# BQ27541.net
KiCad netlist of a schematic drawn in EAGLE
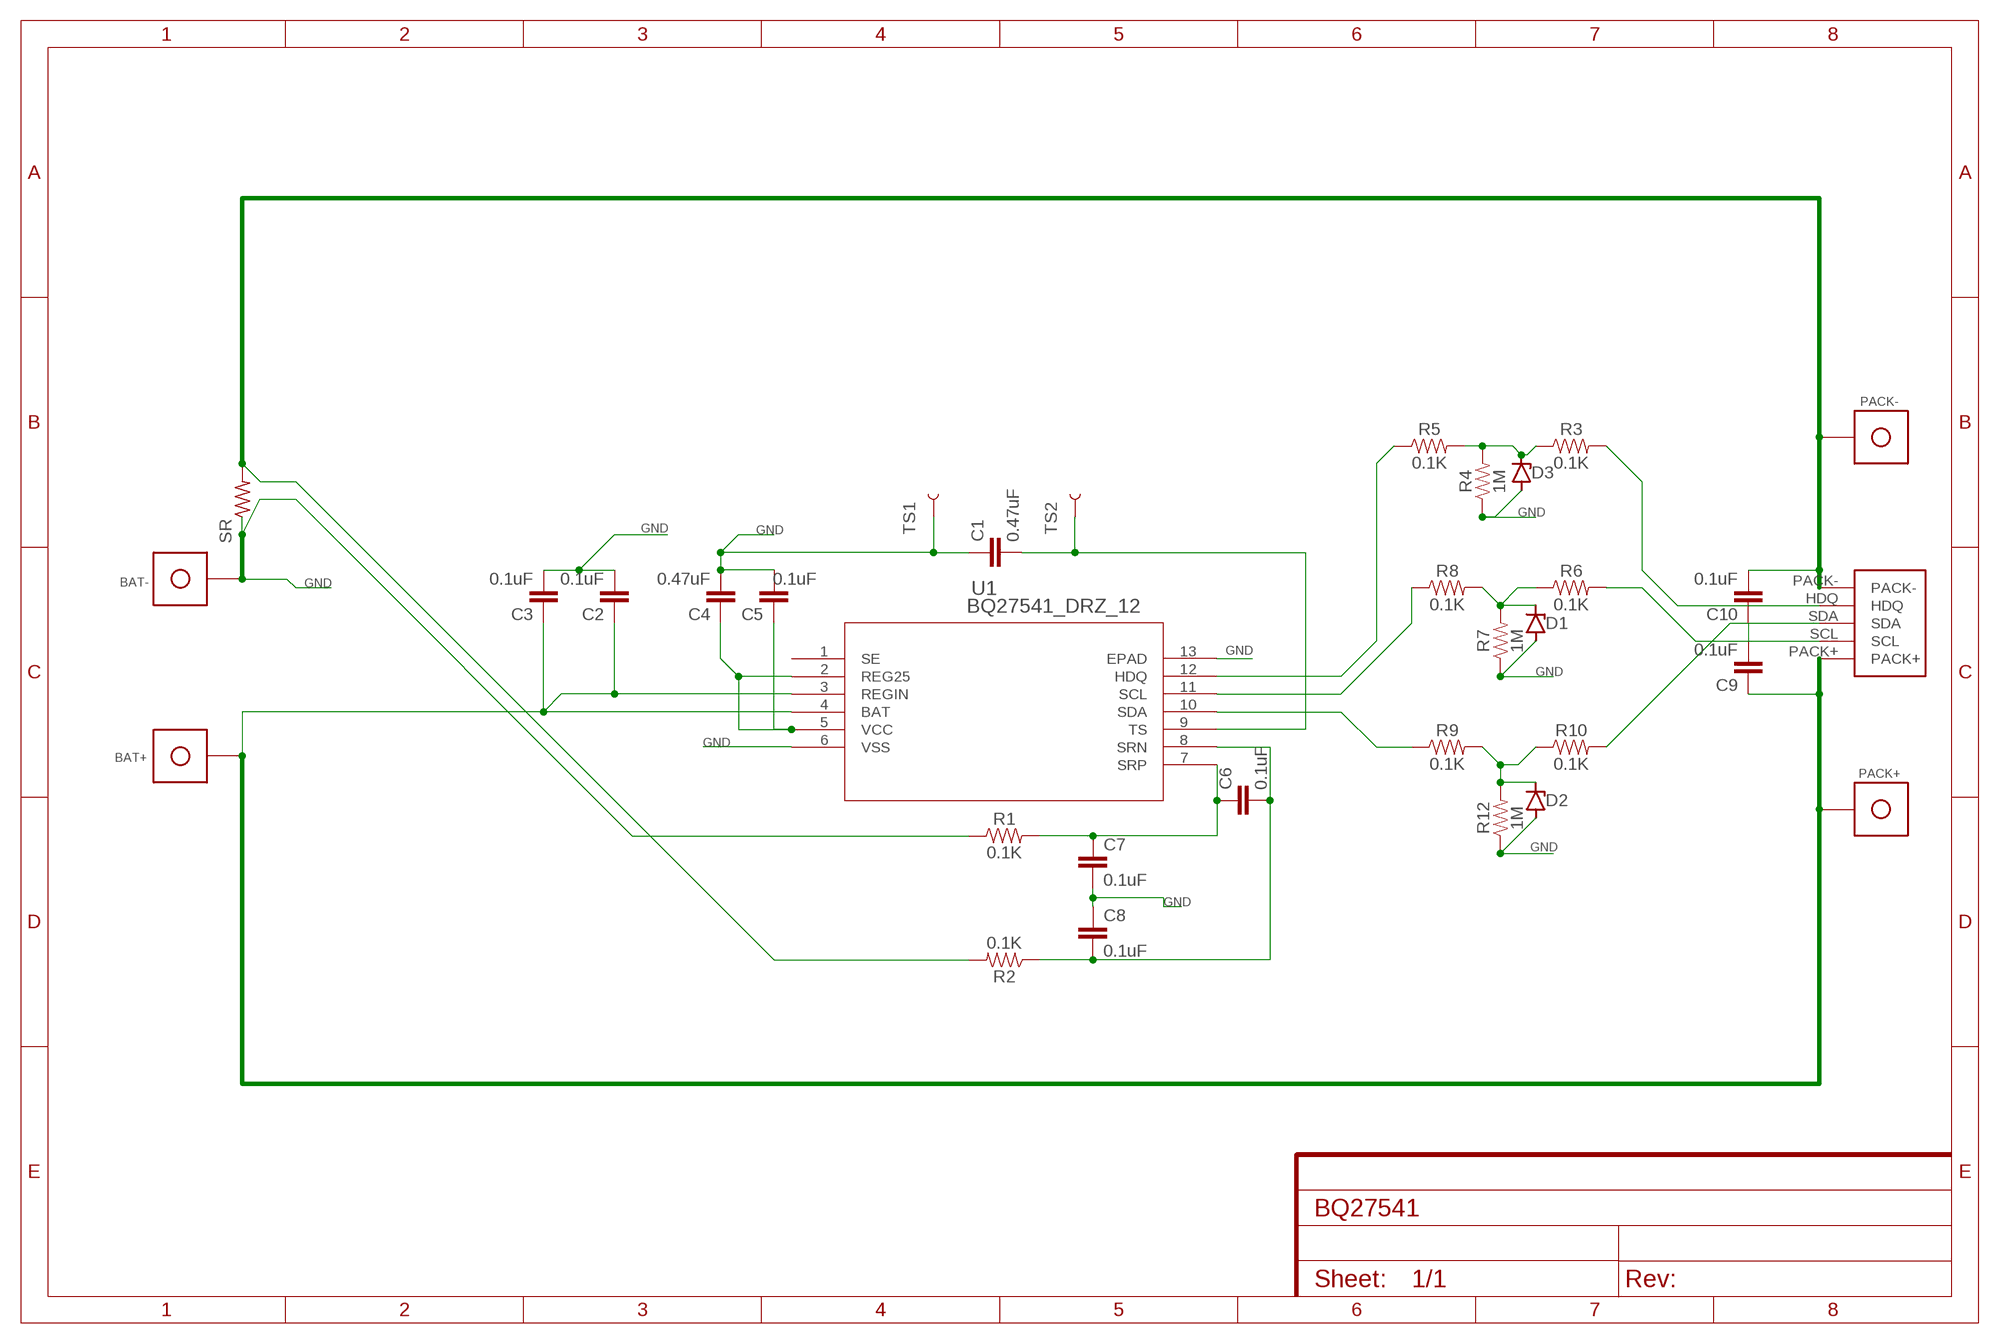
[diagram p0: schematic, sheet 1]

(export (version "E")
  (design (tool "Eeschema 10.0.6"))
  (components
    (comp (ref "BAT+")
      (value "BAT_TAB")
      (footprint "eagle-import:BATT_TAB")
      (libsource (lib "eagle-import") (part "BAT_TAB"))
    )
    (comp (ref "BAT-")
      (value "BAT_TAB")
      (footprint "eagle-import:BATT_TAB")
      (libsource (lib "eagle-import") (part "BAT_TAB"))
    )
    (comp (ref "C1")
      (value "0.47uF")
      (footprint "eagle-import:0402")
      (libsource (lib "eagle-import") (part "0.1UF-0402-16V-10%"))
    )
    (comp (ref "C2")
      (value "0.1uF")
      (footprint "eagle-import:0402")
      (libsource (lib "eagle-import") (part "0.1UF-0402-16V-10%"))
    )
    (comp (ref "C3")
      (value "0.1uF")
      (footprint "eagle-import:0402")
      (libsource (lib "eagle-import") (part "0.1UF-0402-16V-10%"))
    )
    (comp (ref "C4")
      (value "0.47uF")
      (footprint "eagle-import:0402")
      (libsource (lib "eagle-import") (part "0.1UF-0402-16V-10%"))
    )
    (comp (ref "C5")
      (value "0.1uF")
      (footprint "eagle-import:0402")
      (libsource (lib "eagle-import") (part "0.1UF-0402-16V-10%"))
    )
    (comp (ref "C6")
      (value "0.1uF")
      (footprint "eagle-import:0402")
      (libsource (lib "eagle-import") (part "0.1UF-0402-16V-10%"))
    )
    (comp (ref "C7")
      (value "0.1uF")
      (footprint "eagle-import:0402")
      (libsource (lib "eagle-import") (part "0.1UF-0402-16V-10%"))
    )
    (comp (ref "C8")
      (value "0.1uF")
      (footprint "eagle-import:0402")
      (libsource (lib "eagle-import") (part "0.1UF-0402-16V-10%"))
    )
    (comp (ref "C9")
      (value "0.1uF")
      (footprint "eagle-import:0402")
      (libsource (lib "eagle-import") (part "0.1UF-0402-16V-10%"))
    )
    (comp (ref "C10")
      (value "0.1uF")
      (footprint "eagle-import:0402")
      (libsource (lib "eagle-import") (part "0.1UF-0402-16V-10%"))
    )
    (comp (ref "D1")
      (value "ZENER-DIODESOD80C")
      (footprint "eagle-import:SOD80C")
      (libsource (lib "eagle-import") (part "ZENER-DIODESOD80C"))
    )
    (comp (ref "D2")
      (value "ZENER-DIODESOD80C")
      (footprint "eagle-import:SOD80C")
      (libsource (lib "eagle-import") (part "ZENER-DIODESOD80C"))
    )
    (comp (ref "D3")
      (value "ZENER-DIODESOD80C")
      (footprint "eagle-import:SOD80C")
      (libsource (lib "eagle-import") (part "ZENER-DIODESOD80C"))
    )
    (comp (ref "PACK+")
      (value "BAT_TAB")
      (footprint "eagle-import:BATT_TAB")
      (libsource (lib "eagle-import") (part "BAT_TAB"))
    )
    (comp (ref "PACK-")
      (value "BAT_TAB")
      (footprint "eagle-import:BATT_TAB")
      (libsource (lib "eagle-import") (part "BAT_TAB"))
    )
    (comp (ref "R1")
      (value "0.1K")
      (footprint "eagle-import:0402")
      (libsource (lib "eagle-import") (part "22OHM-0402-1/10W-1%"))
    )
    (comp (ref "R2")
      (value "0.1K")
      (footprint "eagle-import:0402")
      (libsource (lib "eagle-import") (part "22OHM-0402-1/10W-1%"))
    )
    (comp (ref "R3")
      (value "0.1K")
      (footprint "eagle-import:0402")
      (libsource (lib "eagle-import") (part "22OHM-0402-1/10W-1%"))
    )
    (comp (ref "R4")
      (value "1M")
      (footprint "eagle-import:0402")
      (libsource (lib "eagle-import") (part "22OHM-0402-1/10W-1%"))
    )
    (comp (ref "R5")
      (value "0.1K")
      (footprint "eagle-import:0402")
      (libsource (lib "eagle-import") (part "22OHM-0402-1/10W-1%"))
    )
    (comp (ref "R6")
      (value "0.1K")
      (footprint "eagle-import:0402")
      (libsource (lib "eagle-import") (part "22OHM-0402-1/10W-1%"))
    )
    (comp (ref "R7")
      (value "1M")
      (footprint "eagle-import:0402")
      (libsource (lib "eagle-import") (part "22OHM-0402-1/10W-1%"))
    )
    (comp (ref "R8")
      (value "0.1K")
      (footprint "eagle-import:0402")
      (libsource (lib "eagle-import") (part "22OHM-0402-1/10W-1%"))
    )
    (comp (ref "R9")
      (value "0.1K")
      (footprint "eagle-import:0402")
      (libsource (lib "eagle-import") (part "22OHM-0402-1/10W-1%"))
    )
    (comp (ref "R10")
      (value "0.1K")
      (footprint "eagle-import:0402")
      (libsource (lib "eagle-import") (part "22OHM-0402-1/10W-1%"))
    )
    (comp (ref "R12")
      (value "1M")
      (footprint "eagle-import:0402")
      (libsource (lib "eagle-import") (part "22OHM-0402-1/10W-1%"))
    )
    (comp (ref "SR")
      (value "R-US_R2512")
      (footprint "eagle-import:R2512")
      (libsource (lib "eagle-import") (part "R-US_R2512"))
    )
    (comp (ref "TS1")
      (value "TEST-POINT3X5")
      (footprint "eagle-import:PAD.03X.05")
      (libsource (lib "eagle-import") (part "TEST-POINT3X5"))
    )
    (comp (ref "TS2")
      (value "TEST-POINT3X5")
      (footprint "eagle-import:PAD.03X.05")
      (libsource (lib "eagle-import") (part "TEST-POINT3X5"))
    )
    (comp (ref "U$1")
      (value "BAT_COMM_PWR")
      (footprint "eagle-import:BATT_COMM_PWR")
      (libsource (lib "eagle-import") (part "BAT_COMM_PWR"))
    )
    (comp (ref "U1")
      (value "BQ27541_DRZ_12")
      (footprint "eagle-import:DRZ12_1P95X2P45")
      (fields
        (field (name "GENERIC_PART_NUMBER") "BQ27541")
        (field (name "MANUFACTURER") "Texas Instruments")
      )
      (libsource (lib "eagle-import") (part "BQ27541_DRZ_12"))
    )
  )
  (nets
    (net (code "1") (name "/GND") (class "Default")
      (node (ref "BAT-") (pin "P$1") (pinfunction "P$1_P$1") (pintype "power_in"))
      (node (ref "C1") (pin "1") (pinfunction "1_1") (pintype "passive"))
      (node (ref "C2") (pin "2") (pinfunction "2_2") (pintype "passive"))
      (node (ref "C3") (pin "2") (pinfunction "2_2") (pintype "passive"))
      (node (ref "C4") (pin "2") (pinfunction "2_2") (pintype "passive"))
      (node (ref "C5") (pin "2") (pinfunction "2_2") (pintype "passive"))
      (node (ref "C7") (pin "2") (pinfunction "2_2") (pintype "passive"))
      (node (ref "C8") (pin "1") (pinfunction "1_1") (pintype "passive"))
      (node (ref "D1") (pin "A") (pinfunction "A_A") (pintype "passive"))
      (node (ref "D2") (pin "A") (pinfunction "A_A") (pintype "passive"))
      (node (ref "D3") (pin "A") (pinfunction "A_A") (pintype "passive"))
      (node (ref "R1") (pin "1") (pinfunction "1_1") (pintype "passive"))
      (node (ref "R12") (pin "1") (pinfunction "1_1") (pintype "passive"))
      (node (ref "R4") (pin "1") (pinfunction "1_1") (pintype "passive"))
      (node (ref "R7") (pin "1") (pinfunction "1_1") (pintype "passive"))
      (node (ref "SR") (pin "1") (pinfunction "1_1") (pintype "passive"))
      (node (ref "TS1") (pin "P$1") (pinfunction "1_P$1") (pintype "bidirectional"))
      (node (ref "U1") (pin "13") (pinfunction "EPAD_13") (pintype "power_in"))
      (node (ref "U1") (pin "6") (pinfunction "VSS_6") (pintype "power_in"))
    )
    (net (code "2") (name "Net-(C10-Pad1)") (class "Default")
      (node (ref "C10") (pin "1") (pinfunction "1_1") (pintype "passive"))
      (node (ref "C9") (pin "2") (pinfunction "2_2") (pintype "passive"))
    )
    (net (code "3") (name "Net-(C10-Pad2)") (class "Default")
      (node (ref "C10") (pin "2") (pinfunction "2_2") (pintype "passive"))
      (node (ref "PACK-") (pin "P$1") (pinfunction "P$1_P$1") (pintype "power_in"))
      (node (ref "R2") (pin "2") (pinfunction "2_2") (pintype "passive"))
      (node (ref "SR") (pin "2") (pinfunction "2_2") (pintype "passive"))
      (node (ref "U$1") (pin "PACK-") (pinfunction "PACK-_PACK-") (pintype "power_in"))
    )
    (net (code "4") (name "Net-(D1-PadC)") (class "Default")
      (node (ref "D1") (pin "C") (pinfunction "C_C") (pintype "passive"))
      (node (ref "R6") (pin "1") (pinfunction "1_1") (pintype "passive"))
      (node (ref "R7") (pin "2") (pinfunction "2_2") (pintype "passive"))
      (node (ref "R8") (pin "2") (pinfunction "2_2") (pintype "passive"))
    )
    (net (code "5") (name "Net-(D2-PadC)") (class "Default")
      (node (ref "D2") (pin "C") (pinfunction "C_C") (pintype "passive"))
      (node (ref "R10") (pin "1") (pinfunction "1_1") (pintype "passive"))
      (node (ref "R12") (pin "2") (pinfunction "2_2") (pintype "passive"))
      (node (ref "R9") (pin "2") (pinfunction "2_2") (pintype "passive"))
    )
    (net (code "6") (name "Net-(D3-PadC)") (class "Default")
      (node (ref "D3") (pin "C") (pinfunction "C_C") (pintype "passive"))
      (node (ref "R3") (pin "1") (pinfunction "1_1") (pintype "passive"))
      (node (ref "R4") (pin "2") (pinfunction "2_2") (pintype "passive"))
      (node (ref "R5") (pin "2") (pinfunction "2_2") (pintype "passive"))
    )
    (net (code "7") (name "Net-(R3-Pad2)") (class "Default")
      (node (ref "R3") (pin "2") (pinfunction "2_2") (pintype "passive"))
      (node (ref "U$1") (pin "HDQ") (pinfunction "HDQ_HDQ") (pintype "bidirectional"))
    )
    (net (code "8") (name "Net-(R6-Pad2)") (class "Default")
      (node (ref "R6") (pin "2") (pinfunction "2_2") (pintype "passive"))
      (node (ref "U$1") (pin "SCL") (pinfunction "SCL_SCL") (pintype "bidirectional"))
    )
    (net (code "9") (name "Net-(R10-Pad2)") (class "Default")
      (node (ref "R10") (pin "2") (pinfunction "2_2") (pintype "passive"))
      (node (ref "U$1") (pin "SDA") (pinfunction "SDA_SDA") (pintype "bidirectional"))
    )
    (net (code "10") (name "Net-(TS2-1)") (class "Default")
      (node (ref "C1") (pin "2") (pinfunction "2_2") (pintype "passive"))
      (node (ref "TS2") (pin "P$1") (pinfunction "1_P$1") (pintype "bidirectional"))
      (node (ref "U1") (pin "9") (pinfunction "TS_9") (pintype "input"))
    )
    (net (code "11") (name "Net-(U1-BAT)") (class "Default")
      (node (ref "BAT+") (pin "P$1") (pinfunction "P$1_P$1") (pintype "power_in"))
      (node (ref "C2") (pin "1") (pinfunction "1_1") (pintype "passive"))
      (node (ref "C3") (pin "1") (pinfunction "1_1") (pintype "passive"))
      (node (ref "C9") (pin "1") (pinfunction "1_1") (pintype "passive"))
      (node (ref "PACK+") (pin "P$1") (pinfunction "P$1_P$1") (pintype "power_in"))
      (node (ref "U$1") (pin "PACK+") (pinfunction "PACK+_PACK+") (pintype "power_in"))
      (node (ref "U1") (pin "3") (pinfunction "REGIN_3") (pintype "power_in"))
      (node (ref "U1") (pin "4") (pinfunction "BAT_4") (pintype "input"))
    )
    (net (code "12") (name "Net-(U1-HDQ)") (class "Default")
      (node (ref "R5") (pin "1") (pinfunction "1_1") (pintype "passive"))
      (node (ref "U1") (pin "12") (pinfunction "HDQ_12") (pintype "bidirectional"))
    )
    (net (code "13") (name "Net-(U1-REG25)") (class "Default")
      (node (ref "C4") (pin "1") (pinfunction "1_1") (pintype "passive"))
      (node (ref "C5") (pin "1") (pinfunction "1_1") (pintype "passive"))
      (node (ref "U1") (pin "2") (pinfunction "REG25_2") (pintype "power_in"))
      (node (ref "U1") (pin "5") (pinfunction "VCC_5") (pintype "power_in"))
    )
    (net (code "14") (name "Net-(U1-SCL)") (class "Default")
      (node (ref "R8") (pin "1") (pinfunction "1_1") (pintype "passive"))
      (node (ref "U1") (pin "11") (pinfunction "SCL_11") (pintype "input"))
    )
    (net (code "15") (name "Net-(U1-SDA)") (class "Default")
      (node (ref "R9") (pin "1") (pinfunction "1_1") (pintype "passive"))
      (node (ref "U1") (pin "10") (pinfunction "SDA_10") (pintype "bidirectional"))
    )
    (net (code "16") (name "Net-(U1-SRN)") (class "Default")
      (node (ref "C6") (pin "2") (pinfunction "2_2") (pintype "passive"))
      (node (ref "C8") (pin "2") (pinfunction "2_2") (pintype "passive"))
      (node (ref "R2") (pin "1") (pinfunction "1_1") (pintype "passive"))
      (node (ref "U1") (pin "8") (pinfunction "SRN_8") (pintype "input"))
    )
    (net (code "17") (name "Net-(U1-SRP)") (class "Default")
      (node (ref "C6") (pin "1") (pinfunction "1_1") (pintype "passive"))
      (node (ref "C7") (pin "1") (pinfunction "1_1") (pintype "passive"))
      (node (ref "R1") (pin "2") (pinfunction "2_2") (pintype "passive"))
      (node (ref "U1") (pin "7") (pinfunction "SRP_7") (pintype "input"))
    )
    (net (code "18") (name "unconnected-(U1-SE-Pad1)") (class "Default")
      (node (ref "U1") (pin "1") (pinfunction "SE_1") (pintype "output"))
    )
  )
)
